# MCU.net
KiCad netlist of a schematic drawn in Altium Designer
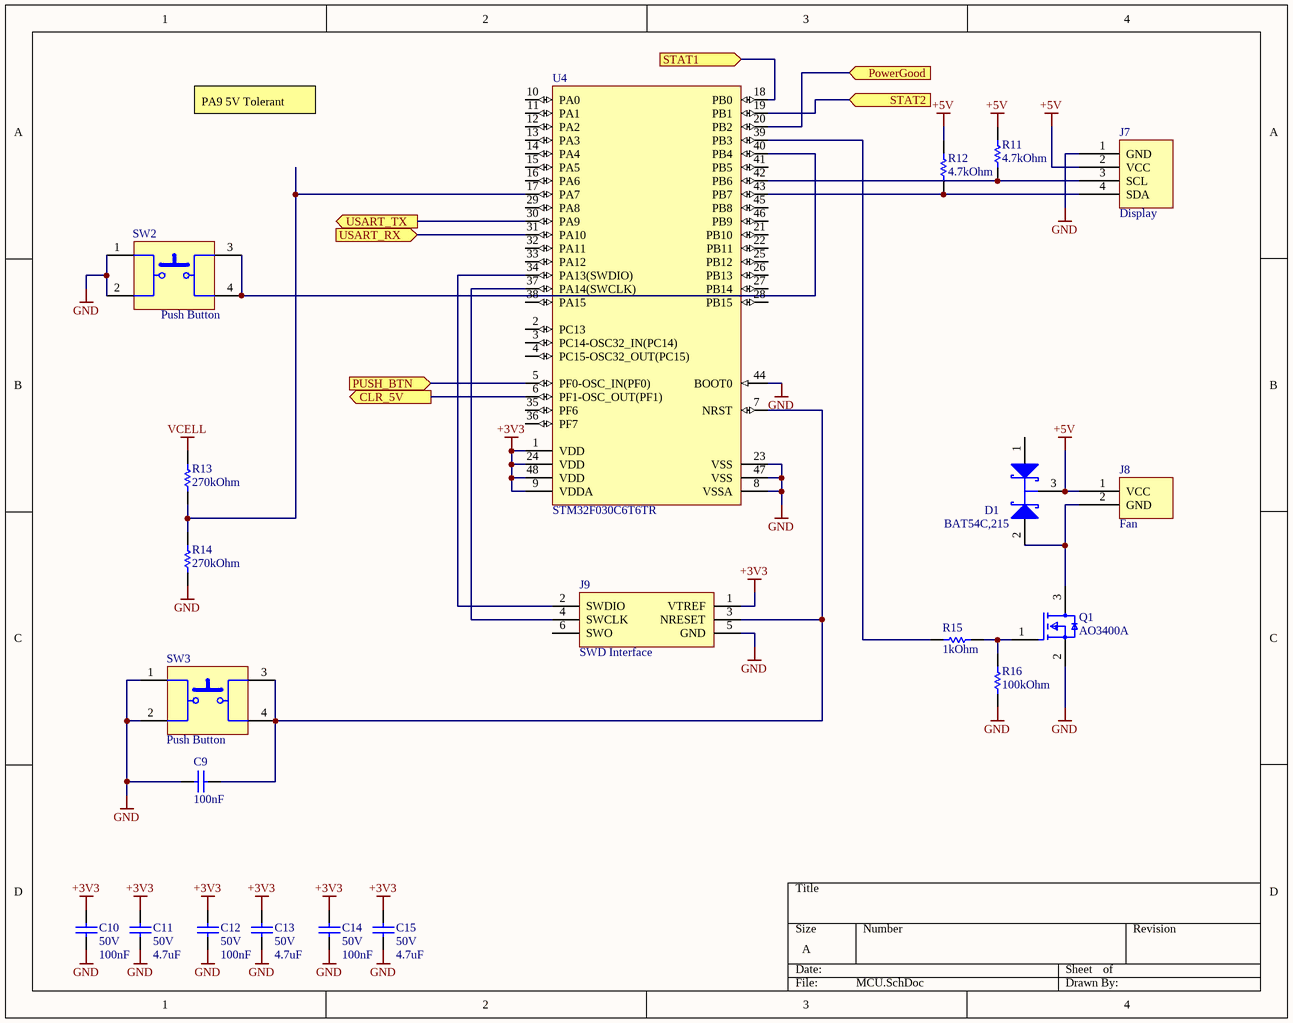
[diagram p0: MCU.SchDoc]

(export (version "E")
  (design (tool "Eeschema 10.0.6"))
  (components
    (comp (ref "C9")
      (value "100nF")
      (footprint "CAP_0804")
      (fields
        (field (name "TOLERANCE") "10%")
        (field (name "PARTNUMBER") "1206GC102KAT1A")
        (field (name "MANUFACTURER") "AVX")
      )
      (libsource (lib "Schlib") (part "CAP_100NF"))
    )
    (comp (ref "C10")
      (value "100nF")
      (footprint "CAPC2013X88X50ML20T25")
      (description "Ceramic Capacitor X7R")
      (fields (field (name "VOLTAGE RATING") "50V") (field (name "Comment") "Cap_0805"))
      (libsource (lib "Ferrofluid_Display") (part "Cap_0805"))
    )
    (comp (ref "C11")
      (value "4.7uF")
      (footprint "CAPC2013X88X50ML20T25")
      (description "Ceramic Capacitor X7R")
      (fields (field (name "VOLTAGE RATING") "50V") (field (name "Comment") "Cap_0805"))
      (libsource (lib "Ferrofluid_Display") (part "Cap_0805"))
    )
    (comp (ref "C12")
      (value "100nF")
      (footprint "CAPC2013X88X50ML20T25")
      (description "Ceramic Capacitor X7R")
      (fields (field (name "VOLTAGE RATING") "50V") (field (name "Comment") "Cap_0805"))
      (libsource (lib "Ferrofluid_Display") (part "Cap_0805"))
    )
    (comp (ref "C13")
      (value "4.7uF")
      (footprint "CAPC2013X88X50ML20T25")
      (description "Ceramic Capacitor X7R")
      (fields (field (name "VOLTAGE RATING") "50V") (field (name "Comment") "Cap_0805"))
      (libsource (lib "Ferrofluid_Display") (part "Cap_0805"))
    )
    (comp (ref "C14")
      (value "100nF")
      (footprint "CAPC2013X88X50ML20T25")
      (description "Ceramic Capacitor X7R")
      (fields (field (name "VOLTAGE RATING") "50V") (field (name "Comment") "Cap_0805"))
      (libsource (lib "Ferrofluid_Display") (part "Cap_0805"))
    )
    (comp (ref "C15")
      (value "4.7uF")
      (footprint "CAPC2013X88X50ML20T25")
      (description "Ceramic Capacitor X7R")
      (fields (field (name "VOLTAGE RATING") "50V") (field (name "Comment") "Cap_0805"))
      (libsource (lib "Ferrofluid_Display") (part "Cap_0805"))
    )
    (comp (ref "D1")
      (value "BAT54C,215")
      (footprint "SOT23")
      (description "Schottky Barrier Diode, 30 V, 3-Pin SOT23, RoHS, Tape and Reel")
      (fields (field (name "MANUFACTURER") "NXP Semiconductors"))
      (libsource (lib "Schlib") (part "DIODE_BAT54C"))
    )
    (comp (ref "J7")
      (value "Display")
      (footprint "OLED_DISPLAY")
      (fields (field (name "MANUFACTURER") "Samtec") (field (name "PARTNUMBER") "MMS-104-01-T-SV"))
      (libsource (lib "Schlib") (part "Oled Display"))
    )
    (comp (ref "J8")
      (value "Fan")
      (footprint "FAN_CONNECTOR")
      (fields (field (name "MANUFACTURER") "Samtec") (field (name "PARTNUMBER") "MMS-104-01-T-SV"))
      (libsource (lib "Schlib") (part "FAN"))
    )
    (comp (ref "J9")
      (value "SWD Interface")
      (footprint "J-Link_6-pin_Needle_Adapter")
      (description "J-Link 6-pin Needle Adapter")
      (libsource (lib "Schlib") (part "J-Link_6-pin_Needle_Adapter"))
    )
    (comp (ref "Q1")
      (value "AO3400A")
      (footprint "SOT23")
      (description "MOSFET N-CH 30V 5.7A SOT23")
      (libsource (lib "Schlib") (part "MOSFET_AO3400A"))
    )
    (comp (ref "R11")
      (value "4.7kOhm")
      (footprint "RES_0804")
      (fields (field (name "PART NUMBER") "CRCW120647K0FKEA") (field (name "MANUFACTURER") "Vishay Dale"))
      (libsource (lib "Schlib") (part "RES_4.7K"))
    )
    (comp (ref "R12")
      (value "4.7kOhm")
      (footprint "RES_0804")
      (fields (field (name "PART NUMBER") "CRCW120647K0FKEA") (field (name "MANUFACTURER") "Vishay Dale"))
      (libsource (lib "Schlib") (part "RES_4.7K"))
    )
    (comp (ref "R13")
      (value "270kOhm")
      (footprint "RES_0804")
      (fields (field (name "PART NUMBER") "CRCW120647K0FKEA") (field (name "MANUFACTURER") "Vishay Dale"))
      (libsource (lib "Schlib") (part "RES_270K"))
    )
    (comp (ref "R14")
      (value "270kOhm")
      (footprint "RES_0804")
      (fields (field (name "PART NUMBER") "CRCW120647K0FKEA") (field (name "MANUFACTURER") "Vishay Dale"))
      (libsource (lib "Schlib") (part "RES_270K"))
    )
    (comp (ref "R15")
      (value "1kOhm")
      (footprint "RES_0804")
      (fields (field (name "PART NUMBER") "CRCW120647K0FKEA") (field (name "MANUFACTURER") "Vishay Dale"))
      (libsource (lib "Schlib") (part "RES_1K"))
    )
    (comp (ref "R16")
      (value "100kOhm")
      (footprint "RES_0804")
      (fields (field (name "PART NUMBER") "CRCW120647K0FKEA") (field (name "MANUFACTURER") "Vishay Dale"))
      (libsource (lib "Schlib") (part "RES_100K"))
    )
    (comp (ref "SW2")
      (value "Push Button")
      (footprint "SWITCH")
      (description "Micro Miniature Push Button Switch FSM JSM, 50 mA, -35 to 85 degC, 4-Pin SMD, RoHS, Tape and Reel")
      (fields (field (name "MANUFACTURER") "TE Connectivity"))
      (libsource (lib "Schlib") (part "SWITCH"))
    )
    (comp (ref "SW3")
      (value "Push Button")
      (footprint "SWITCH")
      (description "Micro Miniature Push Button Switch FSM JSM, 50 mA, -35 to 85 degC, 4-Pin SMD, RoHS, Tape and Reel")
      (fields (field (name "MANUFACTURER") "TE Connectivity"))
      (libsource (lib "Schlib") (part "SWITCH"))
    )
    (comp (ref "U4")
      (value "STM32F030C6T6TR")
      (footprint "STM-LQFP48_M")
      (fields (field (name "MANUFACTURER") "STMicroelectronics"))
      (libsource (lib "Schlib") (part "STM-STM32F030C6-LQFP48_A"))
    )
  )
  (nets
    (net (code "1") (name "+3V3") (class "Default")
      (node (ref "C10") (pin "2") (pinfunction "2_2") (pintype "passive"))
      (node (ref "C11") (pin "2") (pinfunction "2_2") (pintype "passive"))
      (node (ref "C12") (pin "2") (pinfunction "2_2") (pintype "passive"))
      (node (ref "C13") (pin "2") (pinfunction "2_2") (pintype "passive"))
      (node (ref "C14") (pin "2") (pinfunction "2_2") (pintype "passive"))
      (node (ref "C15") (pin "2") (pinfunction "2_2") (pintype "passive"))
      (node (ref "J9") (pin "1") (pinfunction "VTREF_1") (pintype "passive"))
      (node (ref "U4") (pin "1") (pinfunction "VDD_1") (pintype "power_in"))
      (node (ref "U4") (pin "24") (pinfunction "VDD_24") (pintype "power_in"))
      (node (ref "U4") (pin "48") (pinfunction "VDD_48") (pintype "power_in"))
      (node (ref "U4") (pin "9") (pinfunction "VDDA_9") (pintype "power_in"))
    )
    (net (code "2") (name "+5V") (class "Default")
      (node (ref "D1") (pin "3") (pinfunction "K_3") (pintype "passive"))
      (node (ref "J7") (pin "2") (pinfunction "VCC_2") (pintype "passive"))
      (node (ref "J8") (pin "1") (pinfunction "VCC_1") (pintype "passive"))
      (node (ref "R11") (pin "2") (pinfunction "2_2") (pintype "passive"))
      (node (ref "R12") (pin "2") (pinfunction "2_2") (pintype "passive"))
    )
    (net (code "3") (name "/CLR_5V") (class "Default")
      (node (ref "U4") (pin "6") (pinfunction "PF1-OSC_OUT(PF1)_6") (pintype "bidirectional"))
    )
    (net (code "4") (name "/PUSH_BTN") (class "Default")
      (node (ref "U4") (pin "5") (pinfunction "PF0-OSC_IN(PF0)_5") (pintype "bidirectional"))
    )
    (net (code "5") (name "/PowerGood") (class "Default")
      (node (ref "U4") (pin "20") (pinfunction "PB2_20") (pintype "bidirectional"))
    )
    (net (code "6") (name "/STAT1") (class "Default")
      (node (ref "U4") (pin "18") (pinfunction "PB0_18") (pintype "bidirectional"))
    )
    (net (code "7") (name "/STAT2") (class "Default")
      (node (ref "U4") (pin "19") (pinfunction "PB1_19") (pintype "bidirectional"))
    )
    (net (code "8") (name "/USART_RX") (class "Default")
      (node (ref "U4") (pin "31") (pinfunction "PA10_31") (pintype "bidirectional"))
    )
    (net (code "9") (name "/USART_TX") (class "Default")
      (node (ref "U4") (pin "30") (pinfunction "PA9_30") (pintype "bidirectional"))
    )
    (net (code "10") (name "GND") (class "Default")
      (node (ref "C10") (pin "1") (pinfunction "1_1") (pintype "passive"))
      (node (ref "C11") (pin "1") (pinfunction "1_1") (pintype "passive"))
      (node (ref "C12") (pin "1") (pinfunction "1_1") (pintype "passive"))
      (node (ref "C13") (pin "1") (pinfunction "1_1") (pintype "passive"))
      (node (ref "C14") (pin "1") (pinfunction "1_1") (pintype "passive"))
      (node (ref "C15") (pin "1") (pinfunction "1_1") (pintype "passive"))
      (node (ref "C9") (pin "1") (pinfunction "1_1") (pintype "passive"))
      (node (ref "J7") (pin "1") (pinfunction "GND_1") (pintype "passive"))
      (node (ref "J9") (pin "5") (pinfunction "GND_5") (pintype "passive"))
      (node (ref "Q1") (pin "2") (pinfunction "S_2") (pintype "passive"))
      (node (ref "R14") (pin "1") (pinfunction "1_1") (pintype "passive"))
      (node (ref "R16") (pin "1") (pinfunction "1_1") (pintype "passive"))
      (node (ref "SW2") (pin "1") (pinfunction "1_1") (pintype "passive"))
      (node (ref "SW2") (pin "2") (pinfunction "2_2") (pintype "passive"))
      (node (ref "SW3") (pin "1") (pinfunction "1_1") (pintype "passive"))
      (node (ref "SW3") (pin "2") (pinfunction "2_2") (pintype "passive"))
      (node (ref "U4") (pin "23") (pinfunction "VSS_23") (pintype "power_in"))
      (node (ref "U4") (pin "44") (pinfunction "BOOT0_44") (pintype "input"))
      (node (ref "U4") (pin "47") (pinfunction "VSS_47") (pintype "power_in"))
      (node (ref "U4") (pin "8") (pinfunction "VSSA_8") (pintype "power_in"))
    )
    (net (code "11") (name "Net-(J7-SCL)") (class "Default")
      (node (ref "J7") (pin "3") (pinfunction "SCL_3") (pintype "passive"))
      (node (ref "R11") (pin "1") (pinfunction "1_1") (pintype "passive"))
      (node (ref "U4") (pin "42") (pinfunction "PB6_42") (pintype "bidirectional"))
    )
    (net (code "12") (name "Net-(J7-SDA)") (class "Default")
      (node (ref "J7") (pin "4") (pinfunction "SDA_4") (pintype "passive"))
      (node (ref "R12") (pin "1") (pinfunction "1_1") (pintype "passive"))
      (node (ref "U4") (pin "43") (pinfunction "PB7_43") (pintype "bidirectional"))
    )
    (net (code "13") (name "Net-(J8-GND)") (class "Default")
      (node (ref "D1") (pin "2") (pinfunction "A_2") (pintype "passive"))
      (node (ref "J8") (pin "2") (pinfunction "GND_2") (pintype "passive"))
      (node (ref "Q1") (pin "3") (pinfunction "D_3") (pintype "passive"))
    )
    (net (code "14") (name "Net-(J9-NRESET)") (class "Default")
      (node (ref "C9") (pin "2") (pinfunction "2_2") (pintype "passive"))
      (node (ref "J9") (pin "3") (pinfunction "NRESET_3") (pintype "passive"))
      (node (ref "SW3") (pin "3") (pinfunction "3_3") (pintype "passive"))
      (node (ref "SW3") (pin "4") (pinfunction "4_4") (pintype "passive"))
      (node (ref "U4") (pin "7") (pinfunction "NRST_7") (pintype "bidirectional"))
    )
    (net (code "15") (name "Net-(J9-SWCLK)") (class "Default")
      (node (ref "J9") (pin "4") (pinfunction "SWCLK_4") (pintype "passive"))
      (node (ref "U4") (pin "37") (pinfunction "PA14(SWCLK)_37") (pintype "bidirectional"))
    )
    (net (code "16") (name "Net-(J9-SWDIO)") (class "Default")
      (node (ref "J9") (pin "2") (pinfunction "SWDIO_2") (pintype "passive"))
      (node (ref "U4") (pin "34") (pinfunction "PA13(SWDIO)_34") (pintype "bidirectional"))
    )
    (net (code "17") (name "Net-(Q1-G)") (class "Default")
      (node (ref "Q1") (pin "1") (pinfunction "G_1") (pintype "passive"))
      (node (ref "R15") (pin "2") (pinfunction "2_2") (pintype "passive"))
      (node (ref "R16") (pin "2") (pinfunction "2_2") (pintype "passive"))
    )
    (net (code "18") (name "Net-(U4-PA7)") (class "Default")
      (node (ref "R13") (pin "1") (pinfunction "1_1") (pintype "passive"))
      (node (ref "R14") (pin "2") (pinfunction "2_2") (pintype "passive"))
      (node (ref "U4") (pin "17") (pinfunction "PA7_17") (pintype "bidirectional"))
    )
    (net (code "19") (name "Net-(U4-PB3)") (class "Default")
      (node (ref "R15") (pin "1") (pinfunction "1_1") (pintype "passive"))
      (node (ref "U4") (pin "39") (pinfunction "PB3_39") (pintype "bidirectional"))
    )
    (net (code "20") (name "Net-(U4-PB4)") (class "Default")
      (node (ref "SW2") (pin "3") (pinfunction "3_3") (pintype "passive"))
      (node (ref "SW2") (pin "4") (pinfunction "4_4") (pintype "passive"))
      (node (ref "U4") (pin "40") (pinfunction "PB4_40") (pintype "bidirectional"))
    )
    (net (code "21") (name "VCELL") (class "Default")
      (node (ref "R13") (pin "2") (pinfunction "2_2") (pintype "passive"))
    )
    (net (code "22") (name "unconnected-(D1-A-Pad1)") (class "Default")
      (node (ref "D1") (pin "1") (pinfunction "A_1") (pintype "passive"))
    )
    (net (code "23") (name "unconnected-(J9-SWO-Pad6)") (class "Default")
      (node (ref "J9") (pin "6") (pinfunction "SWO_6") (pintype "passive"))
    )
    (net (code "24") (name "unconnected-(U4-PA0-Pad10)") (class "Default")
      (node (ref "U4") (pin "10") (pinfunction "PA0_10") (pintype "bidirectional"))
    )
    (net (code "25") (name "unconnected-(U4-PA1-Pad11)") (class "Default")
      (node (ref "U4") (pin "11") (pinfunction "PA1_11") (pintype "bidirectional"))
    )
    (net (code "26") (name "unconnected-(U4-PA2-Pad12)") (class "Default")
      (node (ref "U4") (pin "12") (pinfunction "PA2_12") (pintype "bidirectional"))
    )
    (net (code "27") (name "unconnected-(U4-PA3-Pad13)") (class "Default")
      (node (ref "U4") (pin "13") (pinfunction "PA3_13") (pintype "bidirectional"))
    )
    (net (code "28") (name "unconnected-(U4-PA4-Pad14)") (class "Default")
      (node (ref "U4") (pin "14") (pinfunction "PA4_14") (pintype "bidirectional"))
    )
    (net (code "29") (name "unconnected-(U4-PA5-Pad15)") (class "Default")
      (node (ref "U4") (pin "15") (pinfunction "PA5_15") (pintype "bidirectional"))
    )
    (net (code "30") (name "unconnected-(U4-PA6-Pad16)") (class "Default")
      (node (ref "U4") (pin "16") (pinfunction "PA6_16") (pintype "bidirectional"))
    )
    (net (code "31") (name "unconnected-(U4-PA8-Pad29)") (class "Default")
      (node (ref "U4") (pin "29") (pinfunction "PA8_29") (pintype "bidirectional"))
    )
    (net (code "32") (name "unconnected-(U4-PA11-Pad32)") (class "Default")
      (node (ref "U4") (pin "32") (pinfunction "PA11_32") (pintype "bidirectional"))
    )
    (net (code "33") (name "unconnected-(U4-PA12-Pad33)") (class "Default")
      (node (ref "U4") (pin "33") (pinfunction "PA12_33") (pintype "bidirectional"))
    )
    (net (code "34") (name "unconnected-(U4-PA15-Pad38)") (class "Default")
      (node (ref "U4") (pin "38") (pinfunction "PA15_38") (pintype "bidirectional"))
    )
    (net (code "35") (name "unconnected-(U4-PB5-Pad41)") (class "Default")
      (node (ref "U4") (pin "41") (pinfunction "PB5_41") (pintype "bidirectional"))
    )
    (net (code "36") (name "unconnected-(U4-PB8-Pad45)") (class "Default")
      (node (ref "U4") (pin "45") (pinfunction "PB8_45") (pintype "bidirectional"))
    )
    (net (code "37") (name "unconnected-(U4-PB9-Pad46)") (class "Default")
      (node (ref "U4") (pin "46") (pinfunction "PB9_46") (pintype "bidirectional"))
    )
    (net (code "38") (name "unconnected-(U4-PB10-Pad21)") (class "Default")
      (node (ref "U4") (pin "21") (pinfunction "PB10_21") (pintype "bidirectional"))
    )
    (net (code "39") (name "unconnected-(U4-PB11-Pad22)") (class "Default")
      (node (ref "U4") (pin "22") (pinfunction "PB11_22") (pintype "bidirectional"))
    )
    (net (code "40") (name "unconnected-(U4-PB12-Pad25)") (class "Default")
      (node (ref "U4") (pin "25") (pinfunction "PB12_25") (pintype "bidirectional"))
    )
    (net (code "41") (name "unconnected-(U4-PB13-Pad26)") (class "Default")
      (node (ref "U4") (pin "26") (pinfunction "PB13_26") (pintype "bidirectional"))
    )
    (net (code "42") (name "unconnected-(U4-PB14-Pad27)") (class "Default")
      (node (ref "U4") (pin "27") (pinfunction "PB14_27") (pintype "bidirectional"))
    )
    (net (code "43") (name "unconnected-(U4-PB15-Pad28)") (class "Default")
      (node (ref "U4") (pin "28") (pinfunction "PB15_28") (pintype "bidirectional"))
    )
    (net (code "44") (name "unconnected-(U4-PC13-Pad2)") (class "Default")
      (node (ref "U4") (pin "2") (pinfunction "PC13_2") (pintype "bidirectional"))
    )
    (net (code "45") (name "unconnected-(U4-PC14-OSC32_IN(PC14)-Pad3)") (class "Default")
      (node (ref "U4") (pin "3") (pinfunction "PC14-OSC32_IN(PC14)_3") (pintype "bidirectional"))
    )
    (net (code "46") (name "unconnected-(U4-PC15-OSC32_OUT(PC15)-Pad4)") (class "Default")
      (node (ref "U4") (pin "4") (pinfunction "PC15-OSC32_OUT(PC15)_4") (pintype "bidirectional"))
    )
    (net (code "47") (name "unconnected-(U4-PF6-Pad35)") (class "Default")
      (node (ref "U4") (pin "35") (pinfunction "PF6_35") (pintype "bidirectional"))
    )
    (net (code "48") (name "unconnected-(U4-PF7-Pad36)") (class "Default")
      (node (ref "U4") (pin "36") (pinfunction "PF7_36") (pintype "bidirectional"))
    )
  )
)
